# modulev2.net
KiCad netlist of a schematic drawn in EAGLE
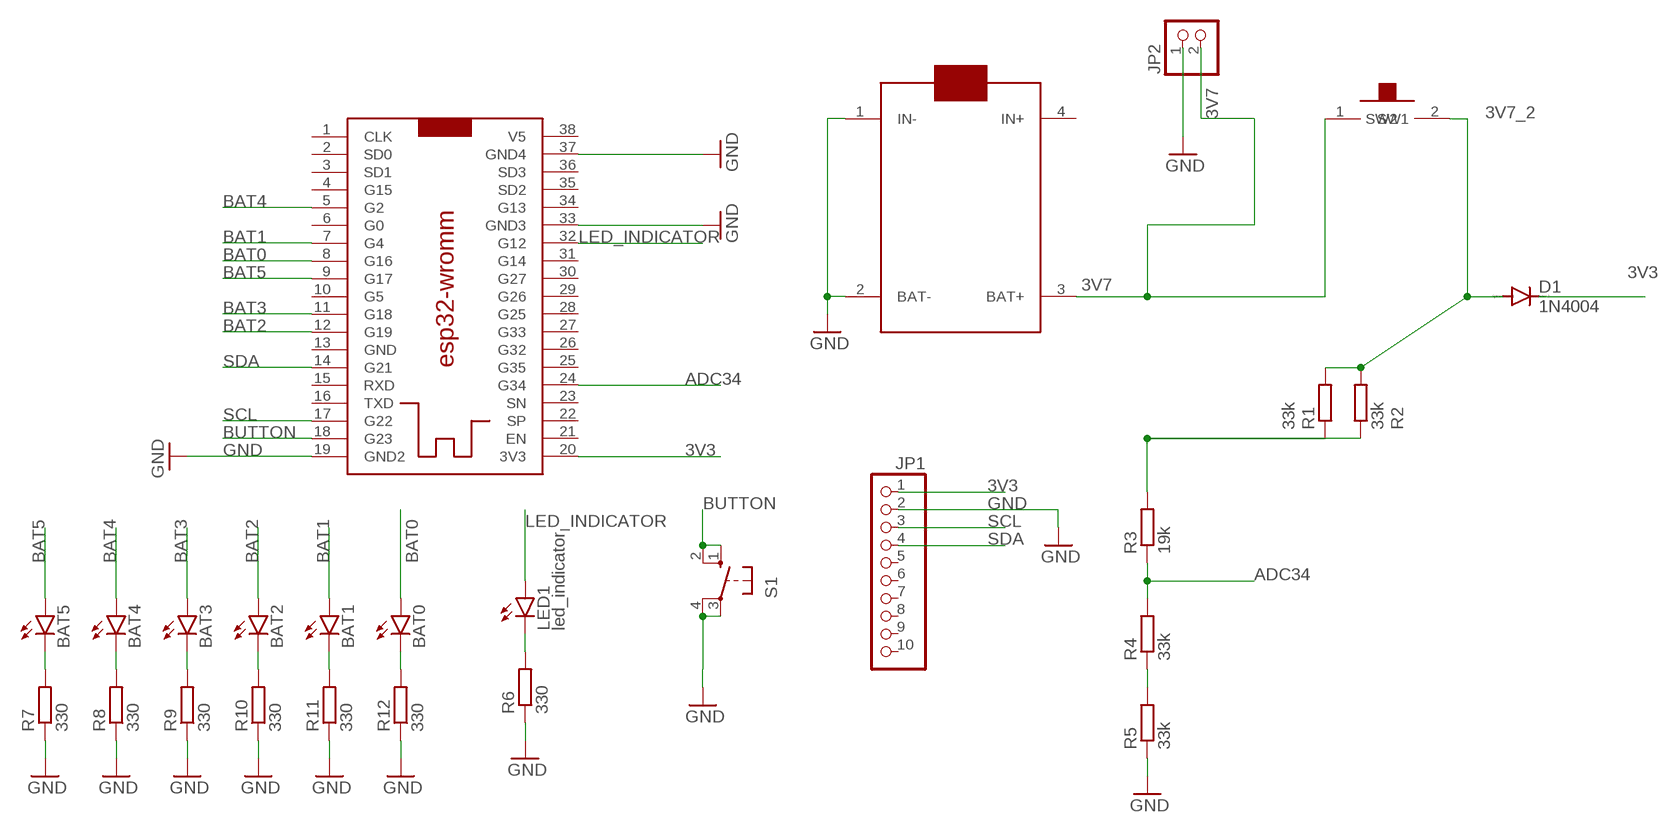
[diagram p0: schematic, sheet 1]

(export (version "E")
  (design (tool "Eeschema 10.0.6"))
  (components
    (comp (ref "BAT0")
      (value "led_indicator")
      (footprint "eagle-import:LED3MM")
      (libsource (lib "eagle-import") (part "LED3MM"))
    )
    (comp (ref "BAT1")
      (value "led_indicator")
      (footprint "eagle-import:LED3MM")
      (libsource (lib "eagle-import") (part "LED3MM"))
    )
    (comp (ref "BAT2")
      (value "led_indicator")
      (footprint "eagle-import:LED3MM")
      (libsource (lib "eagle-import") (part "LED3MM"))
    )
    (comp (ref "BAT3")
      (value "led_indicator")
      (footprint "eagle-import:LED3MM")
      (libsource (lib "eagle-import") (part "LED3MM"))
    )
    (comp (ref "BAT4")
      (value "led_indicator")
      (footprint "eagle-import:LED3MM")
      (libsource (lib "eagle-import") (part "LED3MM"))
    )
    (comp (ref "BAT5")
      (value "led_indicator")
      (footprint "eagle-import:LED3MM")
      (libsource (lib "eagle-import") (part "LED3MM"))
    )
    (comp (ref "D1")
      (value "1N4004")
      (footprint "eagle-import:DO41-10")
      (libsource (lib "eagle-import") (part "1N4004"))
    )
    (comp (ref "JP1")
      (value "PINHD-1X10")
      (footprint "eagle-import:1X10")
      (libsource (lib "eagle-import") (part "PINHD-1X10"))
    )
    (comp (ref "JP2")
      (value "PINHD-1X2")
      (footprint "eagle-import:1X02")
      (libsource (lib "eagle-import") (part "PINHD-1X2"))
    )
    (comp (ref "LED1")
      (value "led_indicator")
      (footprint "eagle-import:LED3MM")
      (libsource (lib "eagle-import") (part "LED3MM"))
    )
    (comp (ref "R1")
      (value "33k")
      (footprint "eagle-import:0204_7")
      (libsource (lib "eagle-import") (part "R-EU_0204/7"))
    )
    (comp (ref "R2")
      (value "33k")
      (footprint "eagle-import:0204_7")
      (libsource (lib "eagle-import") (part "R-EU_0204/7"))
    )
    (comp (ref "R3")
      (value "19k")
      (footprint "eagle-import:0204_7")
      (libsource (lib "eagle-import") (part "R-EU_0204/7"))
    )
    (comp (ref "R4")
      (value "33k")
      (footprint "eagle-import:0204_7")
      (libsource (lib "eagle-import") (part "R-EU_0204/7"))
    )
    (comp (ref "R5")
      (value "33k")
      (footprint "eagle-import:0204_7")
      (libsource (lib "eagle-import") (part "R-EU_0204/7"))
    )
    (comp (ref "R6")
      (value "330")
      (footprint "eagle-import:0204_7")
      (libsource (lib "eagle-import") (part "R-EU_0204/7"))
    )
    (comp (ref "R7")
      (value "330")
      (footprint "eagle-import:0204_7")
      (libsource (lib "eagle-import") (part "R-EU_0204/7"))
    )
    (comp (ref "R8")
      (value "330")
      (footprint "eagle-import:0204_7")
      (libsource (lib "eagle-import") (part "R-EU_0204/7"))
    )
    (comp (ref "R9")
      (value "330")
      (footprint "eagle-import:0204_7")
      (libsource (lib "eagle-import") (part "R-EU_0204/7"))
    )
    (comp (ref "R10")
      (value "330")
      (footprint "eagle-import:0204_7")
      (libsource (lib "eagle-import") (part "R-EU_0204/7"))
    )
    (comp (ref "R11")
      (value "330")
      (footprint "eagle-import:0204_7")
      (libsource (lib "eagle-import") (part "R-EU_0204/7"))
    )
    (comp (ref "R12")
      (value "330")
      (footprint "eagle-import:0204_7")
      (libsource (lib "eagle-import") (part "R-EU_0204/7"))
    )
    (comp (ref "S1")
      (value "10-XX")
      (footprint "eagle-import:B3F-10XX")
      (libsource (lib "eagle-import") (part "10-XX"))
    )
    (comp (ref "U$1")
      (value "ESP32-WROMM2")
      (footprint "eagle-import:ESP32-WORMM2")
      (libsource (lib "eagle-import") (part "ESP32-WROMM2"))
    )
    (comp (ref "U$2")
      (value "CHARGET_MODULE")
      (footprint "eagle-import:CHARGET_MODULE")
      (libsource (lib "eagle-import") (part "CHARGET_MODULE"))
    )
    (comp (ref "U$3")
      (value "MINI_SWITCH")
      (footprint "eagle-import:MINI_SWITCH")
      (libsource (lib "eagle-import") (part "MINI_SWITCH"))
    )
  )
  (nets
    (net (code "1") (name "/3V3") (class "Default")
      (node (ref "D1") (pin "C") (pinfunction "C_C") (pintype "passive"))
      (node (ref "JP1") (pin "1") (pinfunction "1_1") (pintype "passive"))
      (node (ref "U$1") (pin "20") (pinfunction "3V3_20") (pintype "bidirectional"))
    )
    (net (code "2") (name "/3V7") (class "Default")
      (node (ref "JP2") (pin "2") (pinfunction "2_2") (pintype "passive"))
      (node (ref "U$2") (pin "3") (pinfunction "BAT+_3") (pintype "bidirectional"))
      (node (ref "U$3") (pin "1") (pinfunction "SW1_1") (pintype "bidirectional"))
    )
    (net (code "3") (name "/3V7_2") (class "Default")
      (node (ref "D1") (pin "A") (pinfunction "A_A") (pintype "passive"))
      (node (ref "R1") (pin "2") (pinfunction "2_2") (pintype "passive"))
      (node (ref "R2") (pin "2") (pinfunction "2_2") (pintype "passive"))
      (node (ref "U$3") (pin "2") (pinfunction "SW2_2") (pintype "bidirectional"))
    )
    (net (code "4") (name "/ADC34") (class "Default")
      (node (ref "R3") (pin "1") (pinfunction "1_1") (pintype "passive"))
      (node (ref "R4") (pin "2") (pinfunction "2_2") (pintype "passive"))
      (node (ref "U$1") (pin "24") (pinfunction "G34_24") (pintype "bidirectional"))
    )
    (net (code "5") (name "/BAT0") (class "Default")
      (node (ref "BAT0") (pin "A") (pinfunction "A_A") (pintype "passive"))
      (node (ref "U$1") (pin "8") (pinfunction "G16_8") (pintype "bidirectional"))
    )
    (net (code "6") (name "/BAT1") (class "Default")
      (node (ref "BAT1") (pin "A") (pinfunction "A_A") (pintype "passive"))
      (node (ref "U$1") (pin "7") (pinfunction "G4_7") (pintype "bidirectional"))
    )
    (net (code "7") (name "/BAT2") (class "Default")
      (node (ref "BAT2") (pin "A") (pinfunction "A_A") (pintype "passive"))
      (node (ref "U$1") (pin "12") (pinfunction "G19_12") (pintype "bidirectional"))
    )
    (net (code "8") (name "/BAT3") (class "Default")
      (node (ref "BAT3") (pin "A") (pinfunction "A_A") (pintype "passive"))
      (node (ref "U$1") (pin "11") (pinfunction "G18_11") (pintype "bidirectional"))
    )
    (net (code "9") (name "/BAT4") (class "Default")
      (node (ref "BAT4") (pin "A") (pinfunction "A_A") (pintype "passive"))
      (node (ref "U$1") (pin "5") (pinfunction "G2_5") (pintype "bidirectional"))
    )
    (net (code "10") (name "/BAT5") (class "Default")
      (node (ref "BAT5") (pin "A") (pinfunction "A_A") (pintype "passive"))
      (node (ref "U$1") (pin "9") (pinfunction "G17_9") (pintype "bidirectional"))
    )
    (net (code "11") (name "/BUTTON") (class "Default")
      (node (ref "S1") (pin "1") (pinfunction "S_1") (pintype "passive"))
      (node (ref "S1") (pin "2") (pinfunction "S1_2") (pintype "passive"))
      (node (ref "U$1") (pin "18") (pinfunction "G23_18") (pintype "bidirectional"))
    )
    (net (code "12") (name "/LED_INDICATOR") (class "Default")
      (node (ref "LED1") (pin "A") (pinfunction "A_A") (pintype "passive"))
      (node (ref "U$1") (pin "32") (pinfunction "G12_32") (pintype "bidirectional"))
    )
    (net (code "13") (name "/SCL") (class "Default")
      (node (ref "JP1") (pin "3") (pinfunction "3_3") (pintype "passive"))
      (node (ref "U$1") (pin "17") (pinfunction "G22_17") (pintype "bidirectional"))
    )
    (net (code "14") (name "/SDA") (class "Default")
      (node (ref "JP1") (pin "4") (pinfunction "4_4") (pintype "passive"))
      (node (ref "U$1") (pin "14") (pinfunction "G21_14") (pintype "bidirectional"))
    )
    (net (code "15") (name "GND") (class "Default")
      (node (ref "JP1") (pin "2") (pinfunction "2_2") (pintype "passive"))
      (node (ref "JP2") (pin "1") (pinfunction "1_1") (pintype "passive"))
      (node (ref "R10") (pin "1") (pinfunction "1_1") (pintype "passive"))
      (node (ref "R11") (pin "1") (pinfunction "1_1") (pintype "passive"))
      (node (ref "R12") (pin "1") (pinfunction "1_1") (pintype "passive"))
      (node (ref "R5") (pin "1") (pinfunction "1_1") (pintype "passive"))
      (node (ref "R6") (pin "1") (pinfunction "1_1") (pintype "passive"))
      (node (ref "R7") (pin "1") (pinfunction "1_1") (pintype "passive"))
      (node (ref "R8") (pin "1") (pinfunction "1_1") (pintype "passive"))
      (node (ref "R9") (pin "1") (pinfunction "1_1") (pintype "passive"))
      (node (ref "S1") (pin "3") (pinfunction "P_3") (pintype "passive"))
      (node (ref "S1") (pin "4") (pinfunction "P1_4") (pintype "passive"))
      (node (ref "U$1") (pin "19") (pinfunction "GND2_19") (pintype "bidirectional"))
      (node (ref "U$1") (pin "33") (pinfunction "GND3_33") (pintype "bidirectional"))
      (node (ref "U$1") (pin "37") (pinfunction "GND4_37") (pintype "bidirectional"))
      (node (ref "U$2") (pin "1") (pinfunction "IN-_1") (pintype "bidirectional"))
      (node (ref "U$2") (pin "2") (pinfunction "BAT-_2") (pintype "bidirectional"))
    )
    (net (code "16") (name "Net-(BAT0-C)") (class "Default")
      (node (ref "BAT0") (pin "K") (pinfunction "C_K") (pintype "passive"))
      (node (ref "R12") (pin "2") (pinfunction "2_2") (pintype "passive"))
    )
    (net (code "17") (name "Net-(BAT1-C)") (class "Default")
      (node (ref "BAT1") (pin "K") (pinfunction "C_K") (pintype "passive"))
      (node (ref "R11") (pin "2") (pinfunction "2_2") (pintype "passive"))
    )
    (net (code "18") (name "Net-(BAT2-C)") (class "Default")
      (node (ref "BAT2") (pin "K") (pinfunction "C_K") (pintype "passive"))
      (node (ref "R10") (pin "2") (pinfunction "2_2") (pintype "passive"))
    )
    (net (code "19") (name "Net-(BAT3-C)") (class "Default")
      (node (ref "BAT3") (pin "K") (pinfunction "C_K") (pintype "passive"))
      (node (ref "R9") (pin "2") (pinfunction "2_2") (pintype "passive"))
    )
    (net (code "20") (name "Net-(BAT4-C)") (class "Default")
      (node (ref "BAT4") (pin "K") (pinfunction "C_K") (pintype "passive"))
      (node (ref "R8") (pin "2") (pinfunction "2_2") (pintype "passive"))
    )
    (net (code "21") (name "Net-(BAT5-C)") (class "Default")
      (node (ref "BAT5") (pin "K") (pinfunction "C_K") (pintype "passive"))
      (node (ref "R7") (pin "2") (pinfunction "2_2") (pintype "passive"))
    )
    (net (code "22") (name "Net-(LED1-C)") (class "Default")
      (node (ref "LED1") (pin "K") (pinfunction "C_K") (pintype "passive"))
      (node (ref "R6") (pin "2") (pinfunction "2_2") (pintype "passive"))
    )
    (net (code "23") (name "Net-(R1-Pad1)") (class "Default")
      (node (ref "R1") (pin "1") (pinfunction "1_1") (pintype "passive"))
      (node (ref "R2") (pin "1") (pinfunction "1_1") (pintype "passive"))
      (node (ref "R3") (pin "2") (pinfunction "2_2") (pintype "passive"))
    )
    (net (code "24") (name "Net-(R4-Pad1)") (class "Default")
      (node (ref "R4") (pin "1") (pinfunction "1_1") (pintype "passive"))
      (node (ref "R5") (pin "2") (pinfunction "2_2") (pintype "passive"))
    )
    (net (code "25") (name "unconnected-(JP1-Pad5)") (class "Default")
      (node (ref "JP1") (pin "5") (pinfunction "5_5") (pintype "passive"))
    )
    (net (code "26") (name "unconnected-(JP1-Pad6)") (class "Default")
      (node (ref "JP1") (pin "6") (pinfunction "6_6") (pintype "passive"))
    )
    (net (code "27") (name "unconnected-(JP1-Pad7)") (class "Default")
      (node (ref "JP1") (pin "7") (pinfunction "7_7") (pintype "passive"))
    )
    (net (code "28") (name "unconnected-(JP1-Pad8)") (class "Default")
      (node (ref "JP1") (pin "8") (pinfunction "8_8") (pintype "passive"))
    )
    (net (code "29") (name "unconnected-(JP1-Pad9)") (class "Default")
      (node (ref "JP1") (pin "9") (pinfunction "9_9") (pintype "passive"))
    )
    (net (code "30") (name "unconnected-(JP1-Pad10)") (class "Default")
      (node (ref "JP1") (pin "10") (pinfunction "10_10") (pintype "passive"))
    )
    (net (code "31") (name "unconnected-(U$1-CLK-Pad1)") (class "Default")
      (node (ref "U$1") (pin "1") (pinfunction "CLK_1") (pintype "bidirectional"))
    )
    (net (code "32") (name "unconnected-(U$1-EN-Pad21)") (class "Default")
      (node (ref "U$1") (pin "21") (pinfunction "EN_21") (pintype "bidirectional"))
    )
    (net (code "33") (name "unconnected-(U$1-G0-Pad6)") (class "Default")
      (node (ref "U$1") (pin "6") (pinfunction "G0_6") (pintype "bidirectional"))
    )
    (net (code "34") (name "unconnected-(U$1-G5-Pad10)") (class "Default")
      (node (ref "U$1") (pin "10") (pinfunction "G5_10") (pintype "bidirectional"))
    )
    (net (code "35") (name "unconnected-(U$1-G13-Pad34)") (class "Default")
      (node (ref "U$1") (pin "34") (pinfunction "G13_34") (pintype "bidirectional"))
    )
    (net (code "36") (name "unconnected-(U$1-G14-Pad31)") (class "Default")
      (node (ref "U$1") (pin "31") (pinfunction "G14_31") (pintype "bidirectional"))
    )
    (net (code "37") (name "unconnected-(U$1-G15-Pad4)") (class "Default")
      (node (ref "U$1") (pin "4") (pinfunction "G15_4") (pintype "bidirectional"))
    )
    (net (code "38") (name "unconnected-(U$1-G25-Pad28)") (class "Default")
      (node (ref "U$1") (pin "28") (pinfunction "G25_28") (pintype "bidirectional"))
    )
    (net (code "39") (name "unconnected-(U$1-G26-Pad29)") (class "Default")
      (node (ref "U$1") (pin "29") (pinfunction "G26_29") (pintype "bidirectional"))
    )
    (net (code "40") (name "unconnected-(U$1-G27-Pad30)") (class "Default")
      (node (ref "U$1") (pin "30") (pinfunction "G27_30") (pintype "bidirectional"))
    )
    (net (code "41") (name "unconnected-(U$1-G32-Pad26)") (class "Default")
      (node (ref "U$1") (pin "26") (pinfunction "G32_26") (pintype "bidirectional"))
    )
    (net (code "42") (name "unconnected-(U$1-G33-Pad27)") (class "Default")
      (node (ref "U$1") (pin "27") (pinfunction "G33_27") (pintype "bidirectional"))
    )
    (net (code "43") (name "unconnected-(U$1-G35-Pad25)") (class "Default")
      (node (ref "U$1") (pin "25") (pinfunction "G35_25") (pintype "bidirectional"))
    )
    (net (code "44") (name "unconnected-(U$1-GND-Pad13)") (class "Default")
      (node (ref "U$1") (pin "13") (pinfunction "GND_13") (pintype "bidirectional"))
    )
    (net (code "45") (name "unconnected-(U$1-RXD-Pad15)") (class "Default")
      (node (ref "U$1") (pin "15") (pinfunction "RXD_15") (pintype "bidirectional"))
    )
    (net (code "46") (name "unconnected-(U$1-SD0-Pad2)") (class "Default")
      (node (ref "U$1") (pin "2") (pinfunction "SD0_2") (pintype "bidirectional"))
    )
    (net (code "47") (name "unconnected-(U$1-SD1-Pad3)") (class "Default")
      (node (ref "U$1") (pin "3") (pinfunction "SD1_3") (pintype "bidirectional"))
    )
    (net (code "48") (name "unconnected-(U$1-SD2-Pad35)") (class "Default")
      (node (ref "U$1") (pin "35") (pinfunction "SD2_35") (pintype "bidirectional"))
    )
    (net (code "49") (name "unconnected-(U$1-SD3-Pad36)") (class "Default")
      (node (ref "U$1") (pin "36") (pinfunction "SD3_36") (pintype "bidirectional"))
    )
    (net (code "50") (name "unconnected-(U$1-SN-Pad23)") (class "Default")
      (node (ref "U$1") (pin "23") (pinfunction "SN_23") (pintype "bidirectional"))
    )
    (net (code "51") (name "unconnected-(U$1-SP-Pad22)") (class "Default")
      (node (ref "U$1") (pin "22") (pinfunction "SP_22") (pintype "bidirectional"))
    )
    (net (code "52") (name "unconnected-(U$1-TXD-Pad16)") (class "Default")
      (node (ref "U$1") (pin "16") (pinfunction "TXD_16") (pintype "bidirectional"))
    )
    (net (code "53") (name "unconnected-(U$1-V5-Pad38)") (class "Default")
      (node (ref "U$1") (pin "38") (pinfunction "V5_38") (pintype "bidirectional"))
    )
    (net (code "54") (name "unconnected-(U$2-IN+-Pad4)") (class "Default")
      (node (ref "U$2") (pin "4") (pinfunction "IN+_4") (pintype "bidirectional"))
    )
  )
)
